# shiitakevm.net
KiCad netlist of a schematic drawn in EAGLE
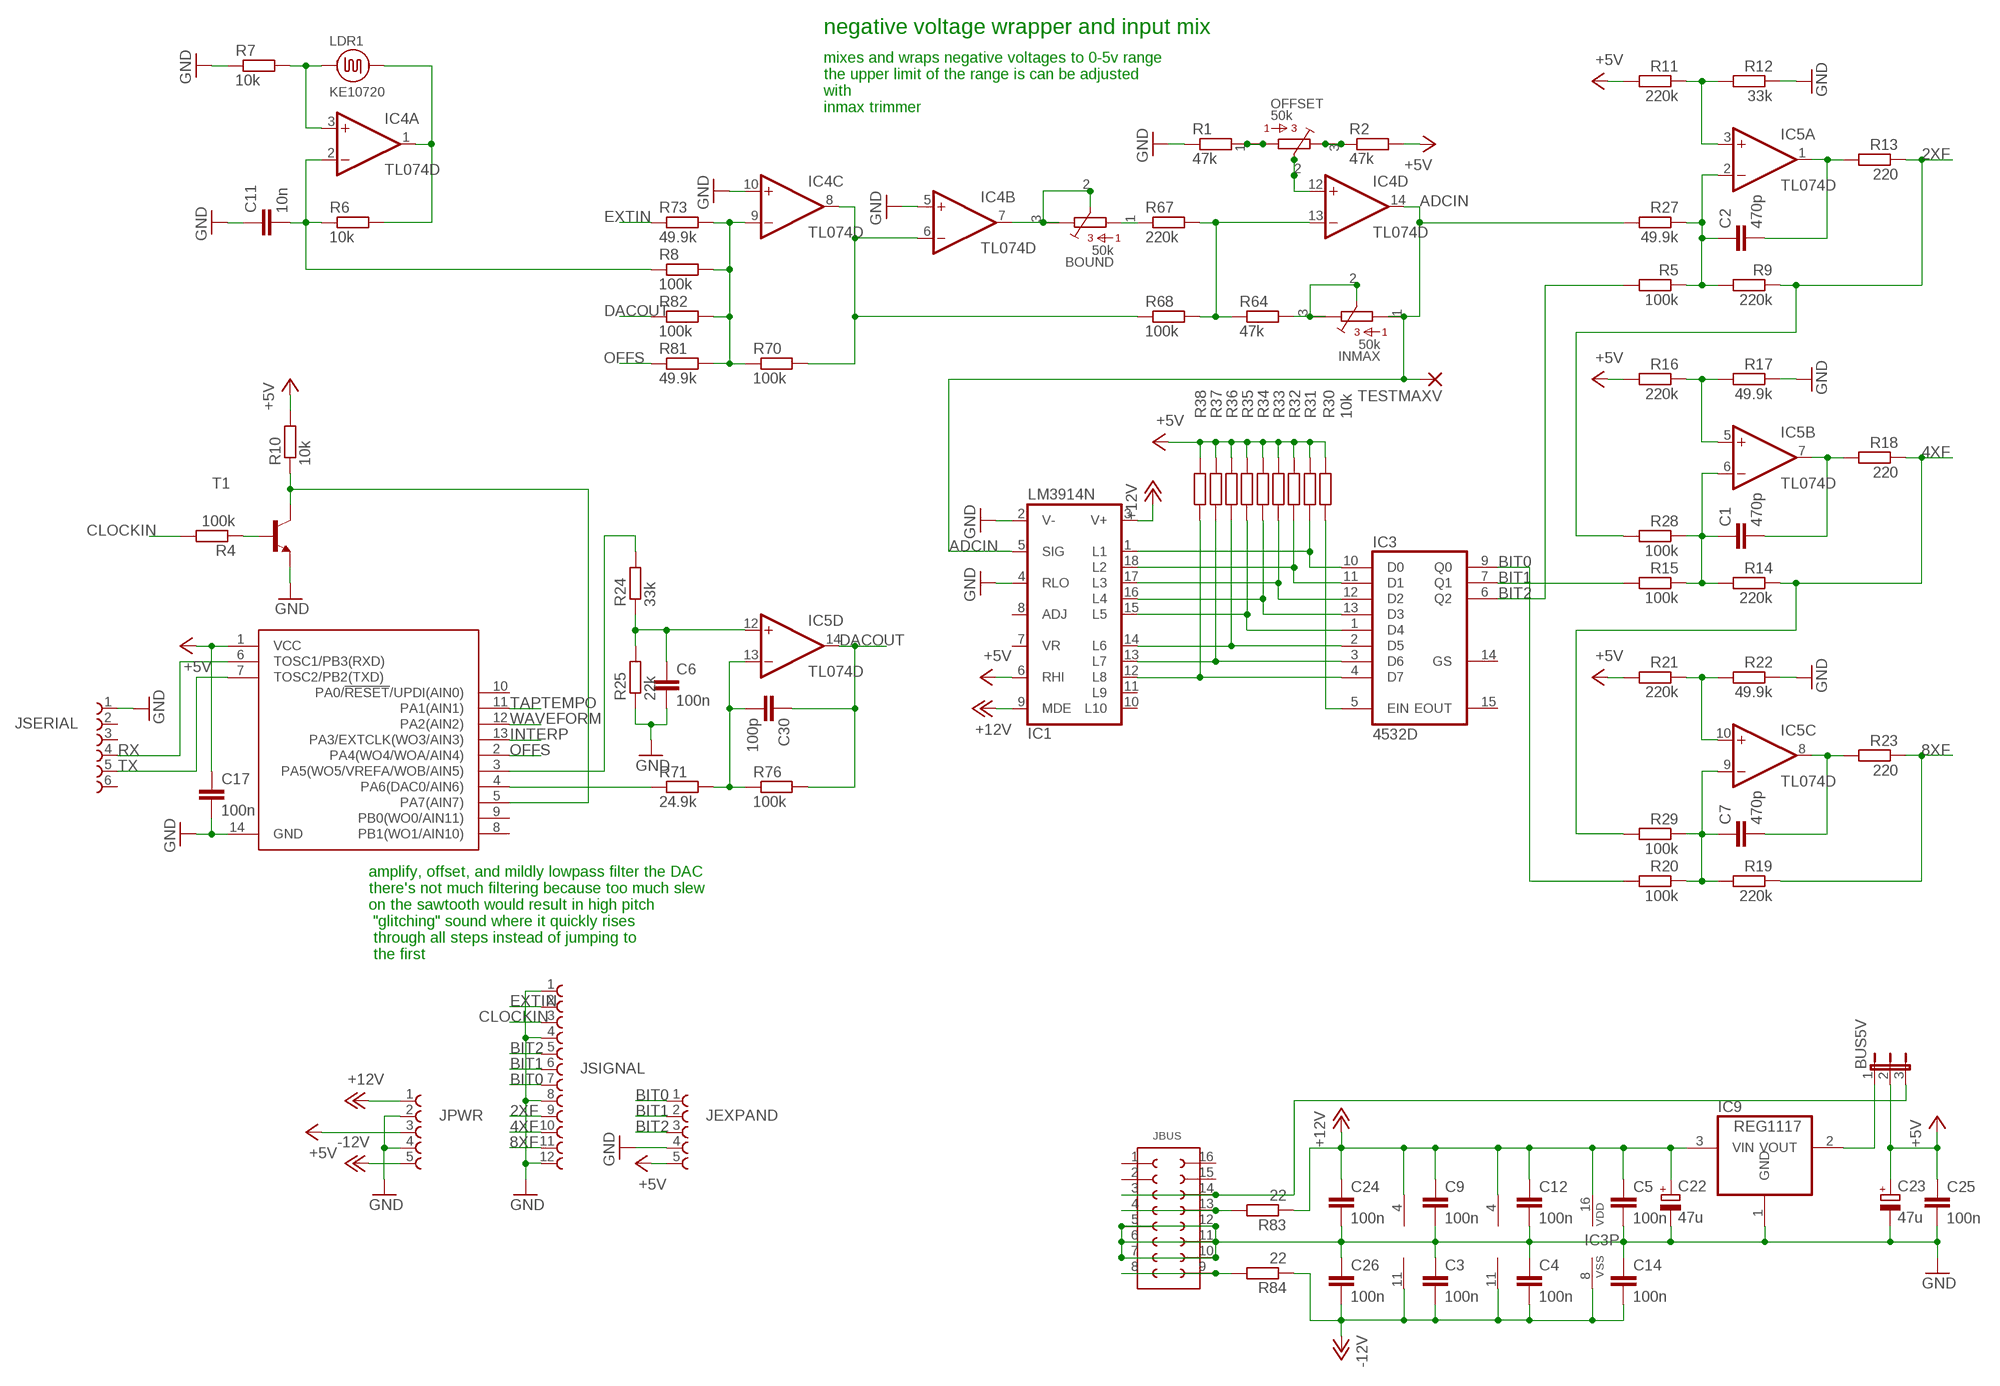
[diagram p0: schematic, sheet 1]

(export (version "E")
  (design (tool "Eeschema 10.0.6"))
  (components
    (comp (ref "BOUND")
      (value "50k")
      (footprint "eagle-import:3386-MULTI")
      (libsource (lib "eagle-import") (part "3386"))
    )
    (comp (ref "BUS5V")
      (value "JP2E")
      (footprint "eagle-import:JP2")
      (libsource (lib "eagle-import") (part "JP2E"))
    )
    (comp (ref "C1")
      (value "470p")
      (footprint "eagle-import:C1206")
      (libsource (lib "eagle-import") (part "C-EUC1206"))
    )
    (comp (ref "C2")
      (value "470p")
      (footprint "eagle-import:C1206")
      (libsource (lib "eagle-import") (part "C-EUC1206"))
    )
    (comp (ref "C3")
      (value "100n")
      (footprint "eagle-import:C1206")
      (libsource (lib "eagle-import") (part "C-EUC1206"))
    )
    (comp (ref "C4")
      (value "100n")
      (footprint "eagle-import:C1206")
      (libsource (lib "eagle-import") (part "C-EUC1206"))
    )
    (comp (ref "C5")
      (value "100n")
      (footprint "eagle-import:C1206")
      (libsource (lib "eagle-import") (part "C-EUC1206"))
    )
    (comp (ref "C6")
      (value "100n")
      (footprint "eagle-import:C1206")
      (libsource (lib "eagle-import") (part "C-EUC1206"))
    )
    (comp (ref "C7")
      (value "470p")
      (footprint "eagle-import:C1206")
      (libsource (lib "eagle-import") (part "C-EUC1206"))
    )
    (comp (ref "C9")
      (value "100n")
      (footprint "eagle-import:C1206")
      (libsource (lib "eagle-import") (part "C-EUC1206"))
    )
    (comp (ref "C11")
      (value "10n")
      (footprint "eagle-import:C1206")
      (libsource (lib "eagle-import") (part "C-EUC1206"))
    )
    (comp (ref "C12")
      (value "100n")
      (footprint "eagle-import:C1206")
      (libsource (lib "eagle-import") (part "C-EUC1206"))
    )
    (comp (ref "C14")
      (value "100n")
      (footprint "eagle-import:C1206")
      (libsource (lib "eagle-import") (part "C-EUC1206"))
    )
    (comp (ref "C17")
      (value "100n")
      (footprint "eagle-import:C1206")
      (libsource (lib "eagle-import") (part "C-EUC1206"))
    )
    (comp (ref "C22")
      (value "47u")
      (footprint "eagle-import:PANASONIC_B")
      (libsource (lib "eagle-import") (part "CPOL-EUB"))
    )
    (comp (ref "C23")
      (value "47u")
      (footprint "eagle-import:PANASONIC_B")
      (libsource (lib "eagle-import") (part "CPOL-EUB"))
    )
    (comp (ref "C24")
      (value "100n")
      (footprint "eagle-import:C1206")
      (libsource (lib "eagle-import") (part "C-EUC1206"))
    )
    (comp (ref "C25")
      (value "100n")
      (footprint "eagle-import:C1206")
      (libsource (lib "eagle-import") (part "C-EUC1206"))
    )
    (comp (ref "C26")
      (value "100n")
      (footprint "eagle-import:C1206")
      (libsource (lib "eagle-import") (part "C-EUC1206"))
    )
    (comp (ref "C30")
      (value "100p")
      (footprint "eagle-import:C1206")
      (libsource (lib "eagle-import") (part "C-EUC1206"))
    )
    (comp (ref "IC1")
      (value "LM3914N")
      (footprint "eagle-import:DIL18")
      (libsource (lib "eagle-import") (part "LM3914N"))
    )
    (comp (ref "IC3")
      (value "4532D")
      (footprint "eagle-import:SO16")
      (libsource (lib "eagle-import") (part "4532D"))
    )
    (comp (ref "IC4")
      (value "TL074D")
      (footprint "eagle-import:SO14")
      (libsource (lib "eagle-import") (part "TL074D"))
    )
    (comp (ref "IC5")
      (value "TL074D")
      (footprint "eagle-import:SO14")
      (libsource (lib "eagle-import") (part "TL074D"))
    )
    (comp (ref "IC9")
      (value "REG1117")
      (footprint "eagle-import:SOT223")
      (libsource (lib "eagle-import") (part "REG1117"))
    )
    (comp (ref "IC11")
      (value "ATTINY1614-SSNR")
      (footprint "eagle-import:SO14")
      (libsource (lib "eagle-import") (part "ATTINY1614-SSNR"))
    )
    (comp (ref "INMAX")
      (value "50k")
      (footprint "eagle-import:3386-MULTI")
      (libsource (lib "eagle-import") (part "3386"))
    )
    (comp (ref "JBUS")
      (value "61301621121")
      (footprint "eagle-import:61301621121")
      (libsource (lib "eagle-import") (part "61301621121"))
    )
    (comp (ref "JEXPAND")
      (value "61300511121")
      (footprint "eagle-import:61300511121")
      (libsource (lib "eagle-import") (part "61300511121"))
    )
    (comp (ref "JPWR")
      (value "61300511121")
      (footprint "eagle-import:61300511121")
      (libsource (lib "eagle-import") (part "61300511121"))
    )
    (comp (ref "JSERIAL")
      (value "61300611821")
      (footprint "eagle-import:61300611821")
      (libsource (lib "eagle-import") (part "61300611821"))
    )
    (comp (ref "JSIGNAL")
      (value "61301211121")
      (footprint "eagle-import:61301211121")
      (libsource (lib "eagle-import") (part "61301211121"))
    )
    (comp (ref "LDR1")
      (value "KE10720")
      (footprint "eagle-import:LDR")
      (libsource (lib "eagle-import") (part "LDR"))
    )
    (comp (ref "OFFSET")
      (value "50k")
      (footprint "eagle-import:3386-MULTI")
      (libsource (lib "eagle-import") (part "3386"))
    )
    (comp (ref "R1")
      (value "47k")
      (footprint "eagle-import:R1206")
      (libsource (lib "eagle-import") (part "R-EU_R1206"))
    )
    (comp (ref "R2")
      (value "47k")
      (footprint "eagle-import:R1206")
      (libsource (lib "eagle-import") (part "R-EU_R1206"))
    )
    (comp (ref "R4")
      (value "100k")
      (footprint "eagle-import:R1206")
      (libsource (lib "eagle-import") (part "R-EU_R1206"))
    )
    (comp (ref "R5")
      (value "100k")
      (footprint "eagle-import:R1206")
      (libsource (lib "eagle-import") (part "R-EU_R1206"))
    )
    (comp (ref "R6")
      (value "10k")
      (footprint "eagle-import:R1206")
      (libsource (lib "eagle-import") (part "R-EU_R1206"))
    )
    (comp (ref "R7")
      (value "10k")
      (footprint "eagle-import:R1206")
      (libsource (lib "eagle-import") (part "R-EU_R1206"))
    )
    (comp (ref "R8")
      (value "100k")
      (footprint "eagle-import:R1206")
      (libsource (lib "eagle-import") (part "R-EU_R1206"))
    )
    (comp (ref "R9")
      (value "220k")
      (footprint "eagle-import:R1206")
      (libsource (lib "eagle-import") (part "R-EU_R1206"))
    )
    (comp (ref "R10")
      (value "10k")
      (footprint "eagle-import:R1206")
      (libsource (lib "eagle-import") (part "R-EU_R1206"))
    )
    (comp (ref "R11")
      (value "220k")
      (footprint "eagle-import:R1206")
      (libsource (lib "eagle-import") (part "R-EU_R1206"))
    )
    (comp (ref "R12")
      (value "33k")
      (footprint "eagle-import:R1206")
      (libsource (lib "eagle-import") (part "R-EU_R1206"))
    )
    (comp (ref "R13")
      (value "220")
      (footprint "eagle-import:R1206")
      (libsource (lib "eagle-import") (part "R-EU_R1206"))
    )
    (comp (ref "R14")
      (value "220k")
      (footprint "eagle-import:R1206")
      (libsource (lib "eagle-import") (part "R-EU_R1206"))
    )
    (comp (ref "R15")
      (value "100k")
      (footprint "eagle-import:R1206")
      (libsource (lib "eagle-import") (part "R-EU_R1206"))
    )
    (comp (ref "R16")
      (value "220k")
      (footprint "eagle-import:R1206")
      (libsource (lib "eagle-import") (part "R-EU_R1206"))
    )
    (comp (ref "R17")
      (value "49.9k")
      (footprint "eagle-import:R1206")
      (libsource (lib "eagle-import") (part "R-EU_R1206"))
    )
    (comp (ref "R18")
      (value "220")
      (footprint "eagle-import:R1206")
      (libsource (lib "eagle-import") (part "R-EU_R1206"))
    )
    (comp (ref "R19")
      (value "220k")
      (footprint "eagle-import:R1206")
      (libsource (lib "eagle-import") (part "R-EU_R1206"))
    )
    (comp (ref "R20")
      (value "100k")
      (footprint "eagle-import:R1206")
      (libsource (lib "eagle-import") (part "R-EU_R1206"))
    )
    (comp (ref "R21")
      (value "220k")
      (footprint "eagle-import:R1206")
      (libsource (lib "eagle-import") (part "R-EU_R1206"))
    )
    (comp (ref "R22")
      (value "49.9k")
      (footprint "eagle-import:R1206")
      (libsource (lib "eagle-import") (part "R-EU_R1206"))
    )
    (comp (ref "R23")
      (value "220")
      (footprint "eagle-import:R1206")
      (libsource (lib "eagle-import") (part "R-EU_R1206"))
    )
    (comp (ref "R24")
      (value "33k")
      (footprint "eagle-import:R1206")
      (libsource (lib "eagle-import") (part "R-EU_R1206"))
    )
    (comp (ref "R25")
      (value "22k")
      (footprint "eagle-import:R1206")
      (libsource (lib "eagle-import") (part "R-EU_R1206"))
    )
    (comp (ref "R27")
      (value "49.9k")
      (footprint "eagle-import:R1206")
      (libsource (lib "eagle-import") (part "R-EU_R1206"))
    )
    (comp (ref "R28")
      (value "100k")
      (footprint "eagle-import:R1206")
      (libsource (lib "eagle-import") (part "R-EU_R1206"))
    )
    (comp (ref "R29")
      (value "100k")
      (footprint "eagle-import:R1206")
      (libsource (lib "eagle-import") (part "R-EU_R1206"))
    )
    (comp (ref "R30")
      (value "10k")
      (footprint "eagle-import:R1206")
      (libsource (lib "eagle-import") (part "R-EU_R1206"))
    )
    (comp (ref "R31")
      (value "10k")
      (footprint "eagle-import:R1206")
      (libsource (lib "eagle-import") (part "R-EU_R1206"))
    )
    (comp (ref "R32")
      (value "10k")
      (footprint "eagle-import:R1206")
      (libsource (lib "eagle-import") (part "R-EU_R1206"))
    )
    (comp (ref "R33")
      (value "10k")
      (footprint "eagle-import:R1206")
      (libsource (lib "eagle-import") (part "R-EU_R1206"))
    )
    (comp (ref "R34")
      (value "10k")
      (footprint "eagle-import:R1206")
      (libsource (lib "eagle-import") (part "R-EU_R1206"))
    )
    (comp (ref "R35")
      (value "10k")
      (footprint "eagle-import:R1206")
      (libsource (lib "eagle-import") (part "R-EU_R1206"))
    )
    (comp (ref "R36")
      (value "10k")
      (footprint "eagle-import:R1206")
      (libsource (lib "eagle-import") (part "R-EU_R1206"))
    )
    (comp (ref "R37")
      (value "10k")
      (footprint "eagle-import:R1206")
      (libsource (lib "eagle-import") (part "R-EU_R1206"))
    )
    (comp (ref "R38")
      (value "10k")
      (footprint "eagle-import:R1206")
      (libsource (lib "eagle-import") (part "R-EU_R1206"))
    )
    (comp (ref "R64")
      (value "47k")
      (footprint "eagle-import:R1206")
      (libsource (lib "eagle-import") (part "R-EU_R1206"))
    )
    (comp (ref "R67")
      (value "220k")
      (footprint "eagle-import:R1206")
      (libsource (lib "eagle-import") (part "R-EU_R1206"))
    )
    (comp (ref "R68")
      (value "100k")
      (footprint "eagle-import:R1206")
      (libsource (lib "eagle-import") (part "R-EU_R1206"))
    )
    (comp (ref "R70")
      (value "100k")
      (footprint "eagle-import:R1206")
      (libsource (lib "eagle-import") (part "R-EU_R1206"))
    )
    (comp (ref "R71")
      (value "24.9k")
      (footprint "eagle-import:R1206")
      (libsource (lib "eagle-import") (part "R-EU_R1206"))
    )
    (comp (ref "R73")
      (value "49.9k")
      (footprint "eagle-import:R1206")
      (libsource (lib "eagle-import") (part "R-EU_R1206"))
    )
    (comp (ref "R76")
      (value "100k")
      (footprint "eagle-import:R1206")
      (libsource (lib "eagle-import") (part "R-EU_R1206"))
    )
    (comp (ref "R81")
      (value "49.9k")
      (footprint "eagle-import:R1206")
      (libsource (lib "eagle-import") (part "R-EU_R1206"))
    )
    (comp (ref "R82")
      (value "100k")
      (footprint "eagle-import:R1206")
      (libsource (lib "eagle-import") (part "R-EU_R1206"))
    )
    (comp (ref "R83")
      (value "22")
      (footprint "eagle-import:R1206")
      (libsource (lib "eagle-import") (part "R-EU_R1206"))
    )
    (comp (ref "R84")
      (value "22")
      (footprint "eagle-import:R1206")
      (libsource (lib "eagle-import") (part "R-EU_R1206"))
    )
    (comp (ref "T1")
      (value "MMBT3904LT1-NPN-SOT23-BEC")
      (footprint "eagle-import:SOT23-BEC")
      (libsource (lib "eagle-import") (part "-NPN-SOT23-BECMMBT3904LT1"))
    )
    (comp (ref "TESTMAXV")
      (value "2,0/0,9-S")
      (footprint "eagle-import:2,0_0,9-S")
      (libsource (lib "eagle-import") (part "2,0/0,9-S"))
    )
  )
  (nets
    (net (code "1") (name "+5V") (class "Default")
      (node (ref "BUS5V") (pin "2") (pinfunction "2_2") (pintype "passive"))
      (node (ref "C17") (pin "1") (pinfunction "1_1") (pintype "passive"))
      (node (ref "C23") (pin "+") (pinfunction "+_+") (pintype "passive"))
      (node (ref "C25") (pin "1") (pinfunction "1_1") (pintype "passive"))
      (node (ref "IC1") (pin "6") (pinfunction "RHI_6") (pintype "input"))
      (node (ref "IC11") (pin "1") (pinfunction "VCC_1") (pintype "bidirectional"))
      (node (ref "JEXPAND") (pin "5") (pinfunction "5_5") (pintype "passive"))
      (node (ref "JPWR") (pin "3") (pinfunction "3_3") (pintype "passive"))
      (node (ref "R10") (pin "2") (pinfunction "2_2") (pintype "passive"))
      (node (ref "R11") (pin "2") (pinfunction "2_2") (pintype "passive"))
      (node (ref "R16") (pin "2") (pinfunction "2_2") (pintype "passive"))
      (node (ref "R2") (pin "2") (pinfunction "2_2") (pintype "passive"))
      (node (ref "R21") (pin "2") (pinfunction "2_2") (pintype "passive"))
      (node (ref "R30") (pin "1") (pinfunction "1_1") (pintype "passive"))
      (node (ref "R31") (pin "2") (pinfunction "2_2") (pintype "passive"))
      (node (ref "R32") (pin "2") (pinfunction "2_2") (pintype "passive"))
      (node (ref "R33") (pin "2") (pinfunction "2_2") (pintype "passive"))
      (node (ref "R34") (pin "2") (pinfunction "2_2") (pintype "passive"))
      (node (ref "R35") (pin "2") (pinfunction "2_2") (pintype "passive"))
      (node (ref "R36") (pin "2") (pinfunction "2_2") (pintype "passive"))
      (node (ref "R37") (pin "2") (pinfunction "2_2") (pintype "passive"))
      (node (ref "R38") (pin "2") (pinfunction "2_2") (pintype "passive"))
    )
    (net (code "2") (name "+12V") (class "Default")
      (node (ref "C12") (pin "1") (pinfunction "1_1") (pintype "passive"))
      (node (ref "C22") (pin "+") (pinfunction "+_+") (pintype "passive"))
      (node (ref "C24") (pin "1") (pinfunction "1_1") (pintype "passive"))
      (node (ref "C5") (pin "1") (pinfunction "1_1") (pintype "passive"))
      (node (ref "C9") (pin "1") (pinfunction "1_1") (pintype "passive"))
      (node (ref "IC1") (pin "3") (pinfunction "V+_3") (pintype "power_in"))
      (node (ref "IC1") (pin "9") (pinfunction "MDE_9") (pintype "input"))
      (node (ref "IC3") (pin "16") (pinfunction "VDD_16") (pintype "power_in"))
      (node (ref "IC4") (pin "4") (pinfunction "V+_4") (pintype "power_in"))
      (node (ref "IC5") (pin "4") (pinfunction "V+_4") (pintype "power_in"))
      (node (ref "IC9") (pin "3") (pinfunction "VIN_3") (pintype "input"))
      (node (ref "JPWR") (pin "1") (pinfunction "1_1") (pintype "passive"))
      (node (ref "R83") (pin "1") (pinfunction "1_1") (pintype "passive"))
    )
    (net (code "3") (name "-12V") (class "Default")
      (node (ref "C14") (pin "2") (pinfunction "2_2") (pintype "passive"))
      (node (ref "C26") (pin "2") (pinfunction "2_2") (pintype "passive"))
      (node (ref "C3") (pin "2") (pinfunction "2_2") (pintype "passive"))
      (node (ref "C4") (pin "2") (pinfunction "2_2") (pintype "passive"))
      (node (ref "IC3") (pin "8") (pinfunction "VSS_8") (pintype "power_in"))
      (node (ref "IC4") (pin "11") (pinfunction "V-_11") (pintype "power_in"))
      (node (ref "IC5") (pin "11") (pinfunction "V-_11") (pintype "power_in"))
      (node (ref "JPWR") (pin "5") (pinfunction "5_5") (pintype "passive"))
      (node (ref "R84") (pin "1") (pinfunction "1_1") (pintype "passive"))
    )
    (net (code "4") (name "/2XF") (class "Default")
      (node (ref "JSIGNAL") (pin "9") (pinfunction "9_9") (pintype "passive"))
      (node (ref "R13") (pin "1") (pinfunction "1_1") (pintype "passive"))
      (node (ref "R28") (pin "2") (pinfunction "2_2") (pintype "passive"))
      (node (ref "R9") (pin "1") (pinfunction "1_1") (pintype "passive"))
    )
    (net (code "5") (name "/4XF") (class "Default")
      (node (ref "JSIGNAL") (pin "10") (pinfunction "10_10") (pintype "passive"))
      (node (ref "R14") (pin "1") (pinfunction "1_1") (pintype "passive"))
      (node (ref "R18") (pin "1") (pinfunction "1_1") (pintype "passive"))
      (node (ref "R29") (pin "2") (pinfunction "2_2") (pintype "passive"))
    )
    (net (code "6") (name "/8XF") (class "Default")
      (node (ref "JSIGNAL") (pin "11") (pinfunction "11_11") (pintype "passive"))
      (node (ref "R19") (pin "1") (pinfunction "1_1") (pintype "passive"))
      (node (ref "R23") (pin "1") (pinfunction "1_1") (pintype "passive"))
    )
    (net (code "7") (name "/ADCIN") (class "Default")
      (node (ref "IC1") (pin "5") (pinfunction "SIG_5") (pintype "input"))
      (node (ref "IC4") (pin "14") (pinfunction "OUT_14") (pintype "output"))
      (node (ref "INMAX") (pin "1") (pinfunction "1_1") (pintype "passive"))
      (node (ref "INMAX") (pin "4") (pinfunction "4_4") (pintype "passive"))
      (node (ref "R27") (pin "2") (pinfunction "2_2") (pintype "passive"))
      (node (ref "TESTMAXV") (pin "1") (pinfunction "P_1") (pintype "passive"))
    )
    (net (code "8") (name "/BIT0") (class "Default")
      (node (ref "IC3") (pin "9") (pinfunction "Q0_9") (pintype "output"))
      (node (ref "JEXPAND") (pin "1") (pinfunction "1_1") (pintype "passive"))
      (node (ref "JSIGNAL") (pin "7") (pinfunction "7_7") (pintype "passive"))
      (node (ref "R20") (pin "2") (pinfunction "2_2") (pintype "passive"))
    )
    (net (code "9") (name "/BIT1") (class "Default")
      (node (ref "IC3") (pin "7") (pinfunction "Q1_7") (pintype "output"))
      (node (ref "JEXPAND") (pin "2") (pinfunction "2_2") (pintype "passive"))
      (node (ref "JSIGNAL") (pin "6") (pinfunction "6_6") (pintype "passive"))
      (node (ref "R15") (pin "2") (pinfunction "2_2") (pintype "passive"))
    )
    (net (code "10") (name "/BIT2") (class "Default")
      (node (ref "IC3") (pin "6") (pinfunction "Q2_6") (pintype "output"))
      (node (ref "JEXPAND") (pin "3") (pinfunction "3_3") (pintype "passive"))
      (node (ref "JSIGNAL") (pin "5") (pinfunction "5_5") (pintype "passive"))
      (node (ref "R5") (pin "2") (pinfunction "2_2") (pintype "passive"))
    )
    (net (code "11") (name "/CLOCKIN") (class "Default")
      (node (ref "JSIGNAL") (pin "3") (pinfunction "3_3") (pintype "passive"))
      (node (ref "R4") (pin "2") (pinfunction "2_2") (pintype "passive"))
    )
    (net (code "12") (name "/DACOUT") (class "Default")
      (node (ref "C30") (pin "1") (pinfunction "1_1") (pintype "passive"))
      (node (ref "IC5") (pin "14") (pinfunction "OUT_14") (pintype "output"))
      (node (ref "R76") (pin "2") (pinfunction "2_2") (pintype "passive"))
      (node (ref "R82") (pin "1") (pinfunction "1_1") (pintype "passive"))
    )
    (net (code "13") (name "/EXTIN") (class "Default")
      (node (ref "JSIGNAL") (pin "2") (pinfunction "2_2") (pintype "passive"))
      (node (ref "R73") (pin "1") (pinfunction "1_1") (pintype "passive"))
    )
    (net (code "14") (name "/INTERP") (class "Default")
      (node (ref "IC11") (pin "13") (pinfunction "PA3/EXTCLK(WO3/AIN3)_13") (pintype "bidirectional"))
    )
    (net (code "15") (name "/OFFS") (class "Default")
      (node (ref "IC11") (pin "2") (pinfunction "PA4(WO4/WOA/AIN4)_2") (pintype "bidirectional"))
      (node (ref "R81") (pin "1") (pinfunction "1_1") (pintype "passive"))
    )
    (net (code "16") (name "/RX") (class "Default")
      (node (ref "IC11") (pin "6") (pinfunction "TOSC1/PB3(RXD)_6") (pintype "bidirectional"))
      (node (ref "JSERIAL") (pin "4") (pinfunction "4_4") (pintype "passive"))
    )
    (net (code "17") (name "/TAPTEMPO") (class "Default")
      (node (ref "IC11") (pin "11") (pinfunction "PA1(AIN1)_11") (pintype "bidirectional"))
    )
    (net (code "18") (name "/TX") (class "Default")
      (node (ref "IC11") (pin "7") (pinfunction "TOSC2/PB2(TXD)_7") (pintype "bidirectional"))
      (node (ref "JSERIAL") (pin "5") (pinfunction "5_5") (pintype "passive"))
    )
    (net (code "19") (name "/WAVEFORM") (class "Default")
      (node (ref "IC11") (pin "12") (pinfunction "PA2(AIN2)_12") (pintype "bidirectional"))
    )
    (net (code "20") (name "GND") (class "Default")
      (node (ref "C11") (pin "1") (pinfunction "1_1") (pintype "passive"))
      (node (ref "C12") (pin "2") (pinfunction "2_2") (pintype "passive"))
      (node (ref "C14") (pin "1") (pinfunction "1_1") (pintype "passive"))
      (node (ref "C17") (pin "2") (pinfunction "2_2") (pintype "passive"))
      (node (ref "C22") (pin "-") (pinfunction "-_-") (pintype "passive"))
      (node (ref "C23") (pin "-") (pinfunction "-_-") (pintype "passive"))
      (node (ref "C24") (pin "2") (pinfunction "2_2") (pintype "passive"))
      (node (ref "C25") (pin "2") (pinfunction "2_2") (pintype "passive"))
      (node (ref "C26") (pin "1") (pinfunction "1_1") (pintype "passive"))
      (node (ref "C3") (pin "1") (pinfunction "1_1") (pintype "passive"))
      (node (ref "C4") (pin "1") (pinfunction "1_1") (pintype "passive"))
      (node (ref "C5") (pin "2") (pinfunction "2_2") (pintype "passive"))
      (node (ref "C6") (pin "2") (pinfunction "2_2") (pintype "passive"))
      (node (ref "C9") (pin "2") (pinfunction "2_2") (pintype "passive"))
      (node (ref "IC1") (pin "2") (pinfunction "V-_2") (pintype "power_in"))
      (node (ref "IC1") (pin "4") (pinfunction "RLO_4") (pintype "input"))
      (node (ref "IC11") (pin "14") (pinfunction "GND_14") (pintype "bidirectional"))
      (node (ref "IC4") (pin "10") (pinfunction "+IN_10") (pintype "input"))
      (node (ref "IC4") (pin "5") (pinfunction "+IN_5") (pintype "input"))
      (node (ref "IC9") (pin "1") (pinfunction "GND_1") (pintype "power_in"))
      (node (ref "JBUS") (pin "10") (pinfunction "10_10") (pintype "passive"))
      (node (ref "JBUS") (pin "11") (pinfunction "11_11") (pintype "passive"))
      (node (ref "JBUS") (pin "12") (pinfunction "12_12") (pintype "passive"))
      (node (ref "JBUS") (pin "5") (pinfunction "5_5") (pintype "passive"))
      (node (ref "JBUS") (pin "6") (pinfunction "6_6") (pintype "passive"))
      (node (ref "JBUS") (pin "7") (pinfunction "7_7") (pintype "passive"))
      (node (ref "JEXPAND") (pin "4") (pinfunction "4_4") (pintype "passive"))
      (node (ref "JPWR") (pin "2") (pinfunction "2_2") (pintype "passive"))
      (node (ref "JPWR") (pin "4") (pinfunction "4_4") (pintype "passive"))
      (node (ref "JSERIAL") (pin "1") (pinfunction "1_1") (pintype "passive"))
      (node (ref "JSIGNAL") (pin "1") (pinfunction "1_1") (pintype "passive"))
      (node (ref "JSIGNAL") (pin "12") (pinfunction "12_12") (pintype "passive"))
      (node (ref "JSIGNAL") (pin "4") (pinfunction "4_4") (pintype "passive"))
      (node (ref "JSIGNAL") (pin "8") (pinfunction "8_8") (pintype "passive"))
      (node (ref "R1") (pin "1") (pinfunction "1_1") (pintype "passive"))
      (node (ref "R12") (pin "1") (pinfunction "1_1") (pintype "passive"))
      (node (ref "R17") (pin "1") (pinfunction "1_1") (pintype "passive"))
      (node (ref "R22") (pin "1") (pinfunction "1_1") (pintype "passive"))
      (node (ref "R25") (pin "1") (pinfunction "1_1") (pintype "passive"))
      (node (ref "R7") (pin "1") (pinfunction "1_1") (pintype "passive"))
      (node (ref "T1") (pin "E") (pinfunction "E_E") (pintype "passive"))
    )
    (net (code "21") (name "Net-(BOUND-Pad1)") (class "Default")
      (node (ref "BOUND") (pin "1") (pinfunction "1_1") (pintype "passive"))
      (node (ref "BOUND") (pin "4") (pinfunction "4_4") (pintype "passive"))
      (node (ref "R67") (pin "1") (pinfunction "1_1") (pintype "passive"))
    )
    (net (code "22") (name "Net-(BUS5V-Pad3)") (class "Default")
      (node (ref "BUS5V") (pin "3") (pinfunction "3_3") (pintype "passive"))
      (node (ref "JBUS") (pin "14") (pinfunction "14_14") (pintype "passive"))
      (node (ref "JBUS") (pin "3") (pinfunction "3_3") (pintype "passive"))
    )
    (net (code "23") (name "Net-(IC1-L1)") (class "Default")
      (node (ref "IC1") (pin "1") (pinfunction "L1_1") (pintype "output"))
      (node (ref "IC3") (pin "10") (pinfunction "D0_10") (pintype "input"))
      (node (ref "R31") (pin "1") (pinfunction "1_1") (pintype "passive"))
    )
    (net (code "24") (name "Net-(IC1-L2)") (class "Default")
      (node (ref "IC1") (pin "18") (pinfunction "L2_18") (pintype "output"))
      (node (ref "IC3") (pin "11") (pinfunction "D1_11") (pintype "input"))
      (node (ref "R32") (pin "1") (pinfunction "1_1") (pintype "passive"))
    )
    (net (code "25") (name "Net-(IC1-L3)") (class "Default")
      (node (ref "IC1") (pin "17") (pinfunction "L3_17") (pintype "output"))
      (node (ref "IC3") (pin "12") (pinfunction "D2_12") (pintype "input"))
      (node (ref "R33") (pin "1") (pinfunction "1_1") (pintype "passive"))
    )
    (net (code "26") (name "Net-(IC1-L4)") (class "Default")
      (node (ref "IC1") (pin "16") (pinfunction "L4_16") (pintype "output"))
      (node (ref "IC3") (pin "13") (pinfunction "D3_13") (pintype "input"))
      (node (ref "R34") (pin "1") (pinfunction "1_1") (pintype "passive"))
    )
    (net (code "27") (name "Net-(IC1-L5)") (class "Default")
      (node (ref "IC1") (pin "15") (pinfunction "L5_15") (pintype "output"))
      (node (ref "IC3") (pin "1") (pinfunction "D4_1") (pintype "input"))
      (node (ref "R35") (pin "1") (pinfunction "1_1") (pintype "passive"))
    )
    (net (code "28") (name "Net-(IC1-L6)") (class "Default")
      (node (ref "IC1") (pin "14") (pinfunction "L6_14") (pintype "output"))
      (node (ref "IC3") (pin "2") (pinfunction "D5_2") (pintype "input"))
      (node (ref "R36") (pin "1") (pinfunction "1_1") (pintype "passive"))
    )
    (net (code "29") (name "Net-(IC1-L7)") (class "Default")
      (node (ref "IC1") (pin "13") (pinfunction "L7_13") (pintype "output"))
      (node (ref "IC3") (pin "3") (pinfunction "D6_3") (pintype "input"))
      (node (ref "R37") (pin "1") (pinfunction "1_1") (pintype "passive"))
    )
    (net (code "30") (name "Net-(IC1-L8)") (class "Default")
      (node (ref "IC1") (pin "12") (pinfunction "L8_12") (pintype "output"))
      (node (ref "IC3") (pin "4") (pinfunction "D7_4") (pintype "input"))
      (node (ref "R38") (pin "1") (pinfunction "1_1") (pintype "passive"))
    )
    (net (code "31") (name "Net-(IC3A-EIN)") (class "Default")
      (node (ref "IC3") (pin "5") (pinfunction "EIN_5") (pintype "input"))
      (node (ref "R30") (pin "2") (pinfunction "2_2") (pintype "passive"))
    )
    (net (code "32") (name "Net-(IC4A-+IN)") (class "Default")
      (node (ref "IC4") (pin "3") (pinfunction "+IN_3") (pintype "input"))
      (node (ref "LDR1") (pin "P$1") (pinfunction "4_P$1") (pintype "passive"))
      (node (ref "R7") (pin "2") (pinfunction "2_2") (pintype "passive"))
    )
    (net (code "33") (name "Net-(IC4A--IN)") (class "Default")
      (node (ref "C11") (pin "2") (pinfunction "2_2") (pintype "passive"))
      (node (ref "IC4") (pin "2") (pinfunction "-IN_2") (pintype "input"))
      (node (ref "R6") (pin "1") (pinfunction "1_1") (pintype "passive"))
      (node (ref "R8") (pin "1") (pinfunction "1_1") (pintype "passive"))
    )
    (net (code "34") (name "Net-(IC4A-OUT)") (class "Default")
      (node (ref "IC4") (pin "1") (pinfunction "OUT_1") (pintype "output"))
      (node (ref "LDR1") (pin "P$2") (pinfunction "6_P$2") (pintype "passive"))
      (node (ref "R6") (pin "2") (pinfunction "2_2") (pintype "passive"))
    )
    (net (code "35") (name "Net-(IC4B--IN)") (class "Default")
      (node (ref "IC4") (pin "6") (pinfunction "-IN_6") (pintype "input"))
      (node (ref "IC4") (pin "8") (pinfunction "OUT_8") (pintype "output"))
      (node (ref "R68") (pin "1") (pinfunction "1_1") (pintype "passive"))
      (node (ref "R70") (pin "2") (pinfunction "2_2") (pintype "passive"))
    )
    (net (code "36") (name "Net-(IC4B-OUT)") (class "Default")
      (node (ref "BOUND") (pin "2") (pinfunction "2_2") (pintype "passive"))
      (node (ref "BOUND") (pin "3") (pinfunction "3_3") (pintype "passive"))
      (node (ref "BOUND") (pin "5") (pinfunction "5_5") (pintype "passive"))
      (node (ref "BOUND") (pin "6") (pinfunction "6_6") (pintype "passive"))
      (node (ref "IC4") (pin "7") (pinfunction "OUT_7") (pintype "output"))
    )
    (net (code "37") (name "Net-(IC4C--IN)") (class "Default")
      (node (ref "IC4") (pin "9") (pinfunction "-IN_9") (pintype "input"))
      (node (ref "R70") (pin "1") (pinfunction "1_1") (pintype "passive"))
      (node (ref "R73") (pin "2") (pinfunction "2_2") (pintype "passive"))
      (node (ref "R8") (pin "2") (pinfunction "2_2") (pintype "passive"))
      (node (ref "R81") (pin "2") (pinfunction "2_2") (pintype "passive"))
      (node (ref "R82") (pin "2") (pinfunction "2_2") (pintype "passive"))
    )
    (net (code "38") (name "Net-(IC4D-+IN)") (class "Default")
      (node (ref "IC4") (pin "12") (pinfunction "+IN_12") (pintype "input"))
      (node (ref "OFFSET") (pin "2") (pinfunction "2_2") (pintype "passive"))
      (node (ref "OFFSET") (pin "5") (pinfunction "5_5") (pintype "passive"))
    )
    (net (code "39") (name "Net-(IC4D--IN)") (class "Default")
      (node (ref "IC4") (pin "13") (pinfunction "-IN_13") (pintype "input"))
      (node (ref "R64") (pin "1") (pinfunction "1_1") (pintype "passive"))
      (node (ref "R67") (pin "2") (pinfunction "2_2") (pintype "passive"))
      (node (ref "R68") (pin "2") (pinfunction "2_2") (pintype "passive"))
    )
    (net (code "40") (name "Net-(IC5A-+IN)") (class "Default")
      (node (ref "IC5") (pin "3") (pinfunction "+IN_3") (pintype "input"))
      (node (ref "R11") (pin "1") (pinfunction "1_1") (pintype "passive"))
      (node (ref "R12") (pin "2") (pinfunction "2_2") (pintype "passive"))
    )
    (net (code "41") (name "Net-(IC5A--IN)") (class "Default")
      (node (ref "C2") (pin "1") (pinfunction "1_1") (pintype "passive"))
      (node (ref "IC5") (pin "2") (pinfunction "-IN_2") (pintype "input"))
      (node (ref "R27") (pin "1") (pinfunction "1_1") (pintype "passive"))
      (node (ref "R5") (pin "1") (pinfunction "1_1") (pintype "passive"))
      (node (ref "R9") (pin "2") (pinfunction "2_2") (pintype "passive"))
    )
    (net (code "42") (name "Net-(IC5A-OUT)") (class "Default")
      (node (ref "C2") (pin "2") (pinfunction "2_2") (pintype "passive"))
      (node (ref "IC5") (pin "1") (pinfunction "OUT_1") (pintype "output"))
      (node (ref "R13") (pin "2") (pinfunction "2_2") (pintype "passive"))
    )
    (net (code "43") (name "Net-(IC5B-+IN)") (class "Default")
      (node (ref "IC5") (pin "5") (pinfunction "+IN_5") (pintype "input"))
      (node (ref "R16") (pin "1") (pinfunction "1_1") (pintype "passive"))
      (node (ref "R17") (pin "2") (pinfunction "2_2") (pintype "passive"))
    )
    (net (code "44") (name "Net-(IC5B--IN)") (class "Default")
      (node (ref "C1") (pin "1") (pinfunction "1_1") (pintype "passive"))
      (node (ref "IC5") (pin "6") (pinfunction "-IN_6") (pintype "input"))
      (node (ref "R14") (pin "2") (pinfunction "2_2") (pintype "passive"))
      (node (ref "R15") (pin "1") (pinfunction "1_1") (pintype "passive"))
      (node (ref "R28") (pin "1") (pinfunction "1_1") (pintype "passive"))
    )
    (net (code "45") (name "Net-(IC5B-OUT)") (class "Default")
      (node (ref "C1") (pin "2") (pinfunction "2_2") (pintype "passive"))
      (node (ref "IC5") (pin "7") (pinfunction "OUT_7") (pintype "output"))
      (node (ref "R18") (pin "2") (pinfunction "2_2") (pintype "passive"))
    )
    (net (code "46") (name "Net-(IC5C-+IN)") (class "Default")
      (node (ref "IC5") (pin "10") (pinfunction "+IN_10") (pintype "input"))
      (node (ref "R21") (pin "1") (pinfunction "1_1") (pintype "passive"))
      (node (ref "R22") (pin "2") (pinfunction "2_2") (pintype "passive"))
    )
    (net (code "47") (name "Net-(IC5C--IN)") (class "Default")
      (node (ref "C7") (pin "1") (pinfunction "1_1") (pintype "passive"))
      (node (ref "IC5") (pin "9") (pinfunction "-IN_9") (pintype "input"))
      (node (ref "R19") (pin "2") (pinfunction "2_2") (pintype "passive"))
      (node (ref "R20") (pin "1") (pinfunction "1_1") (pintype "passive"))
      (node (ref "R29") (pin "1") (pinfunction "1_1") (pintype "passive"))
    )
    (net (code "48") (name "Net-(IC5C-OUT)") (class "Default")
      (node (ref "C7") (pin "2") (pinfunction "2_2") (pintype "passive"))
      (node (ref "IC5") (pin "8") (pinfunction "OUT_8") (pintype "output"))
      (node (ref "R23") (pin "2") (pinfunction "2_2") (pintype "passive"))
    )
    (net (code "49") (name "Net-(IC5D-+IN)") (class "Default")
      (node (ref "C6") (pin "1") (pinfunction "1_1") (pintype "passive"))
      (node (ref "IC5") (pin "12") (pinfunction "+IN_12") (pintype "input"))
      (node (ref "R24") (pin "1") (pinfunction "1_1") (pintype "passive"))
      (node (ref "R25") (pin "2") (pinfunction "2_2") (pintype "passive"))
    )
    (net (code "50") (name "Net-(IC5D--IN)") (class "Default")
      (node (ref "C30") (pin "2") (pinfunction "2_2") (pintype "passive"))
      (node (ref "IC5") (pin "13") (pinfunction "-IN_13") (pintype "input"))
      (node (ref "R71") (pin "2") (pinfunction "2_2") (pintype "passive"))
      (node (ref "R76") (pin "1") (pinfunction "1_1") (pintype "passive"))
    )
    (net (code "51") (name "Net-(IC9-VOUT)") (class "Default")
      (node (ref "BUS5V") (pin "1") (pinfunction "1_1") (pintype "passive"))
      (node (ref "IC9") (pin "2") (pinfunction "VOUT_2") (pintype "output"))
    )
    (net (code "52") (name "Net-(IC11-PA5(WO5{slash}VREFA{slash}WOB{slash}AIN5))") (class "Default")
      (node (ref "IC11") (pin "3") (pinfunction "PA5(WO5/VREFA/WOB/AIN5)_3") (pintype "bidirectional"))
      (node (ref "R24") (pin "2") (pinfunction "2_2") (pintype "passive"))
    )
    (net (code "53") (name "Net-(IC11-PA6(DAC0{slash}AIN6))") (class "Default")
      (node (ref "IC11") (pin "4") (pinfunction "PA6(DAC0/AIN6)_4") (pintype "bidirectional"))
      (node (ref "R71") (pin "1") (pinfunction "1_1") (pintype "passive"))
    )
    (net (code "54") (name "Net-(IC11-PA7(AIN7))") (class "Default")
      (node (ref "IC11") (pin "5") (pinfunction "PA7(AIN7)_5") (pintype "bidirectional"))
      (node (ref "R10") (pin "1") (pinfunction "1_1") (pintype "passive"))
      (node (ref "T1") (pin "C") (pinfunction "C_C") (pintype "passive"))
    )
    (net (code "55") (name "Net-(INMAX-Pad2)") (class "Default")
      (node (ref "INMAX") (pin "2") (pinfunction "2_2") (pintype "passive"))
      (node (ref "INMAX") (pin "3") (pinfunction "3_3") (pintype "passive"))
      (node (ref "INMAX") (pin "5") (pinfunction "5_5") (pintype "passive"))
      (node (ref "INMAX") (pin "6") (pinfunction "6_6") (pintype "passive"))
      (node (ref "R64") (pin "2") (pinfunction "2_2") (pintype "passive"))
    )
    (net (code "56") (name "Net-(JBUS-Pad8)") (class "Default")
      (node (ref "JBUS") (pin "8") (pinfunction "8_8") (pintype "passive"))
      (node (ref "JBUS") (pin "9") (pinfunction "9_9") (pintype "passive"))
      (node (ref "R84") (pin "2") (pinfunction "2_2") (pintype "passive"))
    )
    (net (code "57") (name "Net-(JBUS-Pad13)") (class "Default")
      (node (ref "JBUS") (pin "13") (pinfunction "13_13") (pintype "passive"))
      (node (ref "JBUS") (pin "4") (pinfunction "4_4") (pintype "passive"))
      (node (ref "R83") (pin "2") (pinfunction "2_2") (pintype "passive"))
    )
    (net (code "58") (name "Net-(OFFSET-Pad1)") (class "Default")
      (node (ref "OFFSET") (pin "1") (pinfunction "1_1") (pintype "passive"))
      (node (ref "OFFSET") (pin "4") (pinfunction "4_4") (pintype "passive"))
      (node (ref "R1") (pin "2") (pinfunction "2_2") (pintype "passive"))
    )
    (net (code "59") (name "Net-(OFFSET-Pad3)") (class "Default")
      (node (ref "OFFSET") (pin "3") (pinfunction "3_3") (pintype "passive"))
      (node (ref "OFFSET") (pin "6") (pinfunction "6_6") (pintype "passive"))
      (node (ref "R2") (pin "1") (pinfunction "1_1") (pintype "passive"))
    )
    (net (code "60") (name "Net-(R4-Pad1)") (class "Default")
      (node (ref "R4") (pin "1") (pinfunction "1_1") (pintype "passive"))
      (node (ref "T1") (pin "B") (pinfunction "B_B") (pintype "passive"))
    )
    (net (code "61") (name "unconnected-(IC1-ADJ-Pad8)") (class "Default")
      (node (ref "IC1") (pin "8") (pinfunction "ADJ_8") (pintype "input"))
    )
    (net (code "62") (name "unconnected-(IC1-L9-Pad11)") (class "Default")
      (node (ref "IC1") (pin "11") (pinfunction "L9_11") (pintype "output"))
    )
    (net (code "63") (name "unconnected-(IC1-L10-Pad10)") (class "Default")
      (node (ref "IC1") (pin "10") (pinfunction "L10_10") (pintype "output"))
    )
    (net (code "64") (name "unconnected-(IC1-VR-Pad7)") (class "Default")
      (node (ref "IC1") (pin "7") (pinfunction "VR_7") (pintype "output"))
    )
    (net (code "65") (name "unconnected-(IC3A-EOUT-Pad15)") (class "Default")
      (node (ref "IC3") (pin "15") (pinfunction "EOUT_15") (pintype "output"))
    )
    (net (code "66") (name "unconnected-(IC3A-GS-Pad14)") (class "Default")
      (node (ref "IC3") (pin "14") (pinfunction "GS_14") (pintype "output"))
    )
    (net (code "67") (name "unconnected-(IC11-PA0{slash}~{RESET}{slash}UPDI(AIN0)-Pad10)") (class "Default")
      (node (ref "IC11") (pin "10") (pinfunction "PA0/~{RESET}/UPDI(AIN0)_10") (pintype "bidirectional"))
    )
    (net (code "68") (name "unconnected-(IC11-PB0(WO0{slash}AIN11)-Pad9)") (class "Default")
      (node (ref "IC11") (pin "9") (pinfunction "PB0(WO0/AIN11)_9") (pintype "bidirectional"))
    )
    (net (code "69") (name "unconnected-(IC11-PB1(WO1{slash}AIN10)-Pad8)") (class "Default")
      (node (ref "IC11") (pin "8") (pinfunction "PB1(WO1/AIN10)_8") (pintype "bidirectional"))
    )
    (net (code "70") (name "unconnected-(JBUS-Pad1)") (class "Default")
      (node (ref "JBUS") (pin "1") (pinfunction "1_1") (pintype "passive"))
    )
    (net (code "71") (name "unconnected-(JBUS-Pad2)") (class "Default")
      (node (ref "JBUS") (pin "2") (pinfunction "2_2") (pintype "passive"))
    )
    (net (code "72") (name "unconnected-(JBUS-Pad15)") (class "Default")
      (node (ref "JBUS") (pin "15") (pinfunction "15_15") (pintype "passive"))
    )
    (net (code "73") (name "unconnected-(JBUS-Pad16)") (class "Default")
      (node (ref "JBUS") (pin "16") (pinfunction "16_16") (pintype "passive"))
    )
    (net (code "74") (name "unconnected-(JSERIAL-Pad2)") (class "Default")
      (node (ref "JSERIAL") (pin "2") (pinfunction "2_2") (pintype "passive"))
    )
    (net (code "75") (name "unconnected-(JSERIAL-Pad3)") (class "Default")
      (node (ref "JSERIAL") (pin "3") (pinfunction "3_3") (pintype "passive"))
    )
    (net (code "76") (name "unconnected-(JSERIAL-Pad6)") (class "Default")
      (node (ref "JSERIAL") (pin "6") (pinfunction "6_6") (pintype "passive"))
    )
  )
)
